# 5V_Supply_Alt_1.net
KiCad netlist of a schematic drawn in Altium Designer
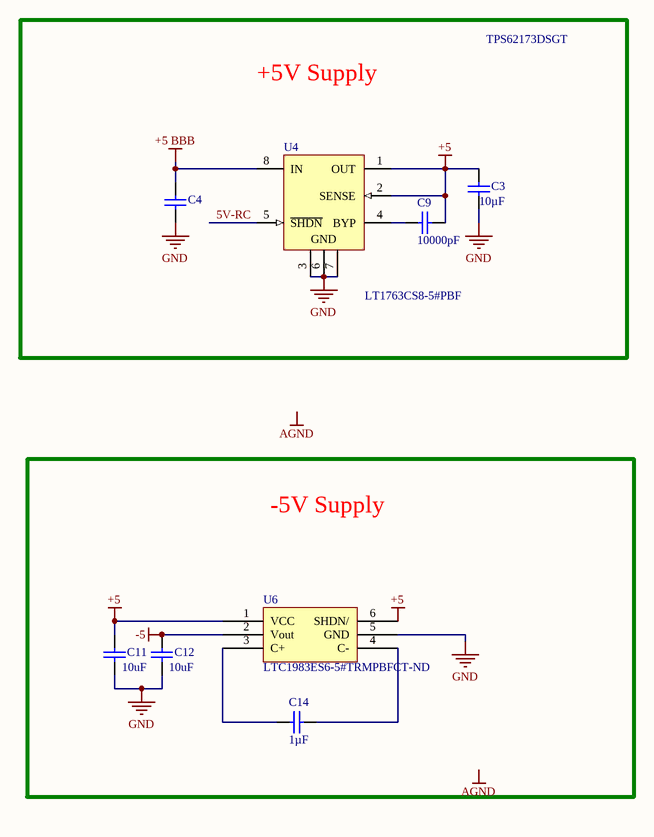
[diagram p0: 5V_Supply_Alt_1.SchDoc]

(export (version "E")
  (design (tool "Eeschema 10.0.6"))
  (components
    (comp (ref "C3")
      (value "CAP CER 1UF 50V X7R 1210")
      (footprint "CAPC1206(3216)130_N")
      (fields
        (field (name "MANUFACTURER") "Murata Electronics North America")
        (field (name "MANUFACTURER PART NUMBER") "GRM32RR71H105KA01L")
        (field (name "CAPACITANCE") "10µF")
        (field (name "TOLERANCE") "±10%")
      )
      (libsource (lib "Altium Content Vault") (part "CMP-1037-04913-1"))
    )
    (comp (ref "C4")
      (value "1uF")
      (footprint "CAPC1206(3216)130_N")
      (libsource (lib "Altium Content Vault") (part "CMP-1037-04913-1"))
    )
    (comp (ref "C9")
      (value "CAP CER 1UF 50V X7R 1210")
      (footprint "CAPC1206(3216)130_N")
      (fields
        (field (name "MANUFACTURER") "Murata Electronics North America")
        (field (name "MANUFACTURER PART NUMBER") "GRM32RR71H105KA01L")
        (field (name "CAPACITANCE") "10000pF")
        (field (name "TOLERANCE") "±10%")
      )
      (libsource (lib "Altium Content Vault") (part "CMP-1037-04913-1"))
    )
    (comp (ref "C11")
      (value "CAP CER 10UF 6.3V X5R 1206")
      (footprint "CAPC1206(3216)130_N")
      (fields
        (field (name "MANUFACTURER") "Taiyo Yuden")
        (field (name "MANUFACTURER PART NUMBER") "JMK316BJ106ML-T")
        (field (name "TOLERANCE") "±20%")
        (field (name "CAPACITANCE") "10uF")
      )
      (libsource (lib "Altium Content Vault") (part "CMP-1037-04913-1"))
    )
    (comp (ref "C12")
      (value "CAP CER 10UF 6.3V X5R 1206")
      (footprint "CAPC1206(3216)130_N")
      (fields
        (field (name "MANUFACTURER") "Taiyo Yuden")
        (field (name "MANUFACTURER PART NUMBER") "JMK316BJ106ML-T")
        (field (name "TOLERANCE") "±20%")
        (field (name "CAPACITANCE") "10uF")
      )
      (libsource (lib "Altium Content Vault") (part "CMP-1037-04913-1"))
    )
    (comp (ref "C14")
      (value "CAP CER 1UF 10V X5R 0805")
      (footprint "CAPC1206(3216)130_N")
      (fields
        (field (name "CAPACITANCE") "1µF")
        (field (name "MANUFACTURER") "Taiyo Yuden")
        (field (name "MANUFACTURER PART NUMBER") "LMK212BJ105MD-T")
        (field (name "TOLERANCE") "±20%")
      )
      (libsource (lib "Altium Content Vault") (part "CMP-1037-04913-1"))
    )
    (comp (ref "U4")
      (value "LT1763CS8-5#PBF")
      (footprint "LT-S8-8_M")
      (fields (field (name "MANUFACTURER") "Linear Technology"))
      (libsource (lib "Altium Content Vault") (part "LT-LT1763-S8-8"))
    )
    (comp (ref "U6")
      (value "LTC1983ES6-5#TRMPBF")
      (footprint "SOT95P323X100-6N")
      (fields
        (field (name "SUPPLIER PART NUMBER 1") "LTC1983ES6-5#TRMPBFCT-ND")
        (field (name "MANUFACTURER") "Linear Technology/Analog Devices")
        (field (name "BASE PART NUMBER") "LTC1983-5")
      )
      (libsource (lib "ZLS_Schematic_lib") (part "LTC1983ES6-5#TRMPBF"))
    )
  )
  (nets
    (net (code "1") (name "+5") (class "Default")
      (node (ref "C11") (pin "2") (pinfunction "2_2") (pintype "passive"))
      (node (ref "C3") (pin "2") (pinfunction "2_2") (pintype "passive"))
      (node (ref "C9") (pin "1") (pinfunction "1_1") (pintype "passive"))
      (node (ref "U4") (pin "1") (pinfunction "OUT_1") (pintype "power_in"))
      (node (ref "U4") (pin "2") (pinfunction "SENSE_2") (pintype "input"))
      (node (ref "U6") (pin "1") (pinfunction "VCC_1") (pintype "passive"))
      (node (ref "U6") (pin "6") (pinfunction "SHDN/_6") (pintype "passive"))
    )
    (net (code "2") (name "+5 BBB") (class "Default")
      (node (ref "C4") (pin "2") (pinfunction "2_2") (pintype "passive"))
      (node (ref "U4") (pin "8") (pinfunction "IN_8") (pintype "power_in"))
    )
    (net (code "3") (name "-5") (class "Default")
      (node (ref "C12") (pin "2") (pinfunction "2_2") (pintype "passive"))
      (node (ref "U6") (pin "2") (pinfunction "Vout_2") (pintype "passive"))
    )
    (net (code "4") (name "/5V-RC") (class "Default")
      (node (ref "U4") (pin "5") (pinfunction "~{SHDN}_5") (pintype "input"))
    )
    (net (code "6") (name "GND") (class "Default")
      (node (ref "C11") (pin "1") (pinfunction "1_1") (pintype "passive"))
      (node (ref "C12") (pin "1") (pinfunction "1_1") (pintype "passive"))
      (node (ref "C3") (pin "1") (pinfunction "1_1") (pintype "passive"))
      (node (ref "C4") (pin "1") (pinfunction "1_1") (pintype "passive"))
      (node (ref "U4") (pin "3") (pinfunction "GND_3") (pintype "power_in"))
      (node (ref "U4") (pin "6") (pinfunction "GND_6") (pintype "power_in"))
      (node (ref "U4") (pin "7") (pinfunction "GND_7") (pintype "power_in"))
      (node (ref "U6") (pin "5") (pinfunction "GND_5") (pintype "passive"))
    )
    (net (code "7") (name "Net-(U4-BYP)") (class "Default")
      (node (ref "C9") (pin "2") (pinfunction "2_2") (pintype "passive"))
      (node (ref "U4") (pin "4") (pinfunction "BYP_4") (pintype "passive"))
    )
    (net (code "8") (name "Net-(U6-C+)") (class "Default")
      (node (ref "C14") (pin "2") (pinfunction "2_2") (pintype "passive"))
      (node (ref "U6") (pin "3") (pinfunction "C+_3") (pintype "passive"))
    )
    (net (code "9") (name "Net-(U6-C-)") (class "Default")
      (node (ref "C14") (pin "1") (pinfunction "1_1") (pintype "passive"))
      (node (ref "U6") (pin "4") (pinfunction "C-_4") (pintype "passive"))
    )
  )
)
